# 02_MCU.net
KiCad netlist of a schematic drawn in Altium Designer
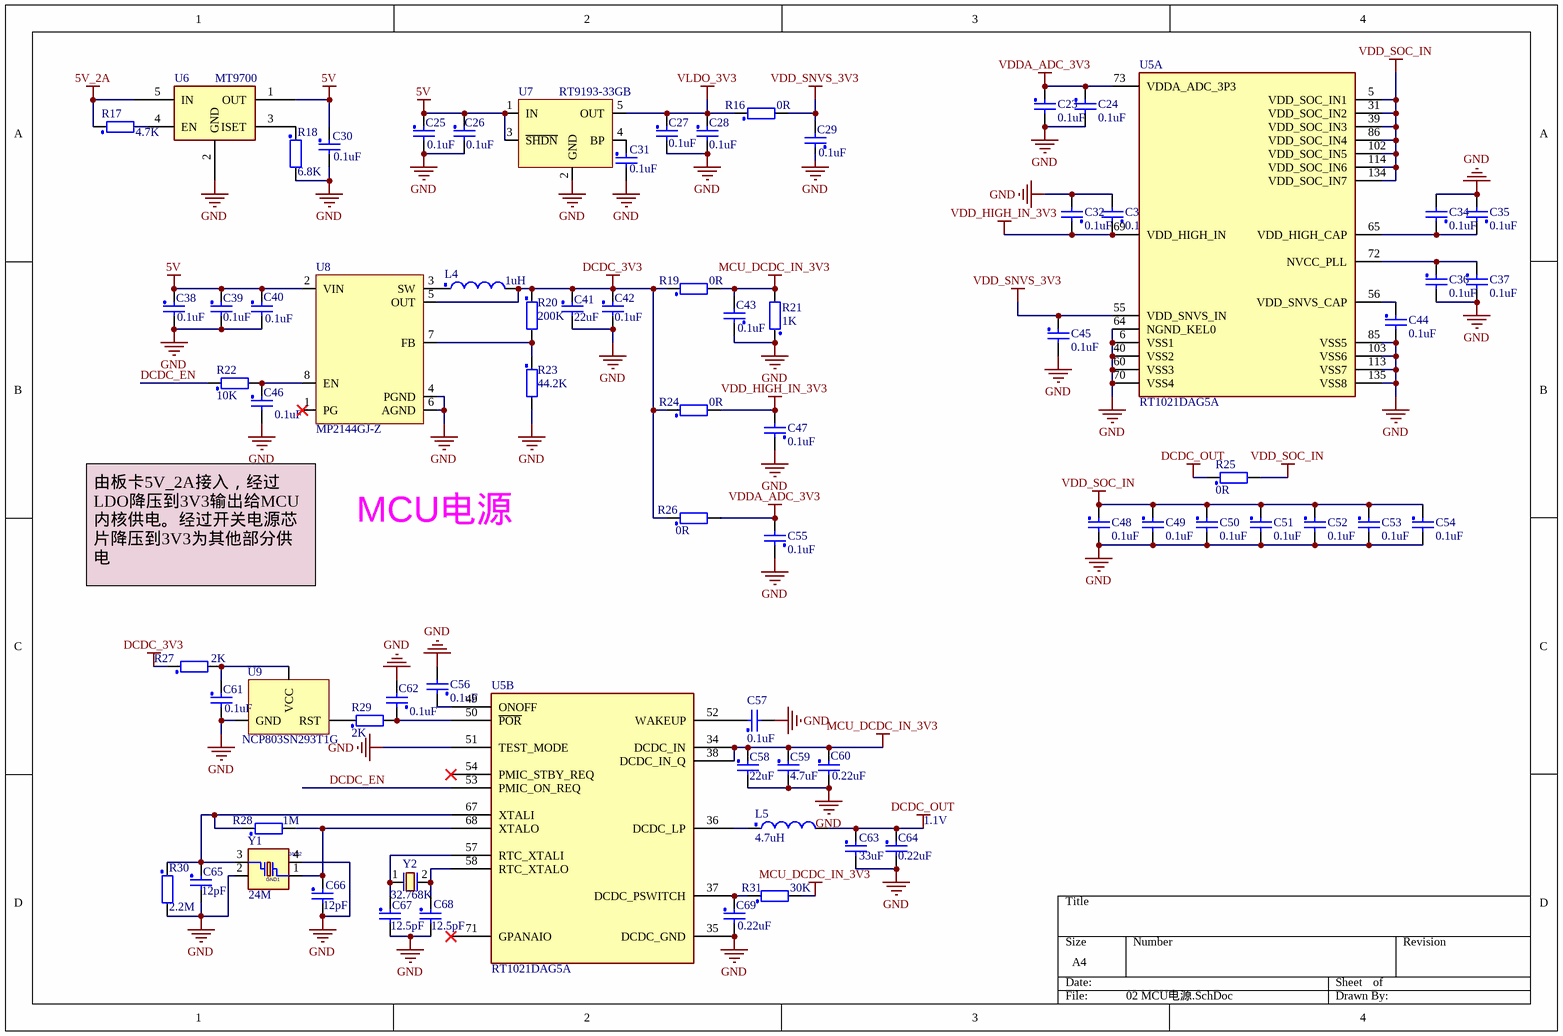
[diagram p0: 02 MCU电源.SchDoc]

(export (version "E")
  (design (tool "Eeschema 10.0.6"))
  (components
    (comp (ref "C23")
      (value "0.1uF")
      (footprint "cap0603")
      (description "贴片电容")
      (fields (field (name "PUBLISHER") "Altium Limited"))
      (libsource (lib "元件库") (part "Cap"))
    )
    (comp (ref "C24")
      (value "0.1uF")
      (footprint "cap0603")
      (description "贴片电容")
      (fields (field (name "PUBLISHER") "Altium Limited"))
      (libsource (lib "元件库") (part "Cap"))
    )
    (comp (ref "C25")
      (value "0.1uF")
      (footprint "cap0603")
      (description "贴片电容")
      (fields (field (name "PUBLISHER") "Altium Limited"))
      (libsource (lib "元件库") (part "Cap"))
    )
    (comp (ref "C26")
      (value "0.1uF")
      (footprint "cap0603")
      (description "贴片电容")
      (fields (field (name "PUBLISHER") "Altium Limited"))
      (libsource (lib "元件库") (part "Cap"))
    )
    (comp (ref "C27")
      (value "0.1uF")
      (footprint "cap0603")
      (description "贴片电容")
      (fields (field (name "PUBLISHER") "Altium Limited"))
      (libsource (lib "元件库") (part "Cap"))
    )
    (comp (ref "C28")
      (value "0.1uF")
      (footprint "cap0603")
      (description "贴片电容")
      (fields (field (name "PUBLISHER") "Altium Limited"))
      (libsource (lib "元件库") (part "Cap"))
    )
    (comp (ref "C29")
      (value "0.1uF")
      (footprint "cap0603")
      (description "贴片电容")
      (fields (field (name "PUBLISHER") "Altium Limited"))
      (libsource (lib "元件库") (part "Cap"))
    )
    (comp (ref "C30")
      (value "0.1uF")
      (footprint "cap0603")
      (description "贴片电容")
      (fields (field (name "PUBLISHER") "Altium Limited"))
      (libsource (lib "元件库") (part "Cap"))
    )
    (comp (ref "C31")
      (value "0.1uF")
      (footprint "cap0603")
      (description "贴片电容")
      (fields (field (name "PUBLISHER") "Altium Limited"))
      (libsource (lib "元件库") (part "Cap"))
    )
    (comp (ref "C32")
      (value "0.1uF")
      (footprint "cap0603")
      (description "贴片电容")
      (fields (field (name "PUBLISHER") "Altium Limited"))
      (libsource (lib "元件库") (part "Cap"))
    )
    (comp (ref "C33")
      (value "0.1uF")
      (footprint "cap0603")
      (description "贴片电容")
      (fields (field (name "PUBLISHER") "Altium Limited"))
      (libsource (lib "元件库") (part "Cap"))
    )
    (comp (ref "C34")
      (value "0.1uF")
      (footprint "cap0603")
      (description "贴片电容")
      (fields (field (name "PUBLISHER") "Altium Limited"))
      (libsource (lib "元件库") (part "Cap"))
    )
    (comp (ref "C35")
      (value "0.1uF")
      (footprint "cap0603")
      (description "贴片电容")
      (fields (field (name "PUBLISHER") "Altium Limited"))
      (libsource (lib "元件库") (part "Cap"))
    )
    (comp (ref "C36")
      (value "0.1uF")
      (footprint "cap0603")
      (description "贴片电容")
      (fields (field (name "PUBLISHER") "Altium Limited"))
      (libsource (lib "元件库") (part "Cap"))
    )
    (comp (ref "C37")
      (value "0.1uF")
      (footprint "cap0603")
      (description "贴片电容")
      (fields (field (name "PUBLISHER") "Altium Limited"))
      (libsource (lib "元件库") (part "Cap"))
    )
    (comp (ref "C38")
      (value "0.1uF")
      (footprint "cap0603")
      (description "贴片电容")
      (fields (field (name "PUBLISHER") "Altium Limited"))
      (libsource (lib "元件库") (part "Cap"))
    )
    (comp (ref "C39")
      (value "0.1uF")
      (footprint "cap0603")
      (description "贴片电容")
      (fields (field (name "PUBLISHER") "Altium Limited"))
      (libsource (lib "元件库") (part "Cap"))
    )
    (comp (ref "C40")
      (value "0.1uF")
      (footprint "cap0603")
      (description "贴片电容")
      (fields (field (name "PUBLISHER") "Altium Limited"))
      (libsource (lib "元件库") (part "Cap"))
    )
    (comp (ref "C41")
      (value "22uF")
      (footprint "CASE-A_3216")
      (description "钽电容")
      (fields (field (name "PUBLISHER") "Altium Limited"))
      (libsource (lib "元件库") (part "Cap"))
    )
    (comp (ref "C42")
      (value "0.1uF")
      (footprint "cap0603")
      (description "贴片电容")
      (fields (field (name "PUBLISHER") "Altium Limited"))
      (libsource (lib "元件库") (part "Cap"))
    )
    (comp (ref "C43")
      (value "0.1uF")
      (footprint "cap0603")
      (description "贴片电容")
      (fields (field (name "PUBLISHER") "Altium Limited"))
      (libsource (lib "元件库") (part "Cap"))
    )
    (comp (ref "C44")
      (value "0.1uF")
      (footprint "cap0603")
      (description "贴片电容")
      (fields (field (name "PUBLISHER") "Altium Limited"))
      (libsource (lib "元件库") (part "Cap"))
    )
    (comp (ref "C45")
      (value "0.1uF")
      (footprint "cap0603")
      (description "贴片电容")
      (fields (field (name "PUBLISHER") "Altium Limited"))
      (libsource (lib "元件库") (part "Cap"))
    )
    (comp (ref "C46")
      (value "0.1uF")
      (footprint "cap0603")
      (description "贴片电容")
      (fields (field (name "PUBLISHER") "Altium Limited"))
      (libsource (lib "元件库") (part "Cap"))
    )
    (comp (ref "C47")
      (value "0.1uF")
      (footprint "cap0603")
      (description "贴片电容")
      (fields (field (name "PUBLISHER") "Altium Limited"))
      (libsource (lib "元件库") (part "Cap"))
    )
    (comp (ref "C48")
      (value "0.1uF")
      (footprint "cap0603")
      (description "贴片电容")
      (fields (field (name "PUBLISHER") "Altium Limited"))
      (libsource (lib "元件库") (part "Cap"))
    )
    (comp (ref "C49")
      (value "0.1uF")
      (footprint "cap0603")
      (description "贴片电容")
      (fields (field (name "PUBLISHER") "Altium Limited"))
      (libsource (lib "元件库") (part "Cap"))
    )
    (comp (ref "C50")
      (value "0.1uF")
      (footprint "cap0603")
      (description "贴片电容")
      (fields (field (name "PUBLISHER") "Altium Limited"))
      (libsource (lib "元件库") (part "Cap"))
    )
    (comp (ref "C51")
      (value "0.1uF")
      (footprint "cap0603")
      (description "贴片电容")
      (fields (field (name "PUBLISHER") "Altium Limited"))
      (libsource (lib "元件库") (part "Cap"))
    )
    (comp (ref "C52")
      (value "0.1uF")
      (footprint "cap0603")
      (description "贴片电容")
      (fields (field (name "PUBLISHER") "Altium Limited"))
      (libsource (lib "元件库") (part "Cap"))
    )
    (comp (ref "C53")
      (value "0.1uF")
      (footprint "cap0603")
      (description "贴片电容")
      (fields (field (name "PUBLISHER") "Altium Limited"))
      (libsource (lib "元件库") (part "Cap"))
    )
    (comp (ref "C54")
      (value "0.1uF")
      (footprint "cap0603")
      (description "贴片电容")
      (fields (field (name "PUBLISHER") "Altium Limited"))
      (libsource (lib "元件库") (part "Cap"))
    )
    (comp (ref "C55")
      (value "0.1uF")
      (footprint "cap0603")
      (description "贴片电容")
      (fields (field (name "PUBLISHER") "Altium Limited"))
      (libsource (lib "元件库") (part "Cap"))
    )
    (comp (ref "C56")
      (value "0.1uF")
      (footprint "cap0603")
      (description "贴片电容")
      (fields (field (name "PUBLISHER") "Altium Limited"))
      (libsource (lib "元件库") (part "Cap"))
    )
    (comp (ref "C57")
      (value "0.1uF")
      (footprint "cap0603")
      (description "贴片电容")
      (fields (field (name "PUBLISHER") "Altium Limited"))
      (libsource (lib "元件库") (part "Cap"))
    )
    (comp (ref "C58")
      (value "22uF")
      (footprint "CASE-A_3216")
      (description "钽电容")
      (fields (field (name "PUBLISHER") "Altium Limited"))
      (libsource (lib "元件库") (part "Cap"))
    )
    (comp (ref "C59")
      (value "4.7uF")
      (footprint "cap0603")
      (description "贴片电容")
      (fields (field (name "PUBLISHER") "Altium Limited"))
      (libsource (lib "元件库") (part "Cap"))
    )
    (comp (ref "C60")
      (value "0.22uF")
      (footprint "cap0603")
      (description "贴片电容")
      (fields (field (name "PUBLISHER") "Altium Limited"))
      (libsource (lib "元件库") (part "Cap"))
    )
    (comp (ref "C61")
      (value "0.1uF")
      (footprint "cap0603")
      (description "贴片电容")
      (fields (field (name "PUBLISHER") "Altium Limited"))
      (libsource (lib "元件库") (part "Cap"))
    )
    (comp (ref "C62")
      (value "0.1uF")
      (footprint "cap0603")
      (description "贴片电容")
      (fields (field (name "PUBLISHER") "Altium Limited"))
      (libsource (lib "元件库") (part "Cap"))
    )
    (comp (ref "C63")
      (value "33uF")
      (footprint "CASE-A_3216")
      (description "钽电容")
      (fields (field (name "PUBLISHER") "Altium Limited"))
      (libsource (lib "元件库") (part "Cap"))
    )
    (comp (ref "C64")
      (value "0.22uF")
      (footprint "cap0603")
      (description "贴片电容")
      (fields (field (name "PUBLISHER") "Altium Limited"))
      (libsource (lib "元件库") (part "Cap"))
    )
    (comp (ref "C65")
      (value "12pF")
      (footprint "cap0603")
      (description "贴片电容")
      (fields (field (name "PUBLISHER") "Altium Limited"))
      (libsource (lib "元件库") (part "Cap"))
    )
    (comp (ref "C66")
      (value "12pF")
      (footprint "cap0603")
      (description "贴片电容")
      (fields (field (name "PUBLISHER") "Altium Limited"))
      (libsource (lib "元件库") (part "Cap"))
    )
    (comp (ref "C67")
      (value "12.5pF")
      (footprint "cap0603")
      (description "贴片电容")
      (fields (field (name "PUBLISHER") "Altium Limited"))
      (libsource (lib "元件库") (part "Cap"))
    )
    (comp (ref "C68")
      (value "12.5pF")
      (footprint "cap0603")
      (description "贴片电容")
      (fields (field (name "PUBLISHER") "Altium Limited"))
      (libsource (lib "元件库") (part "Cap"))
    )
    (comp (ref "C69")
      (value "0.22uF")
      (footprint "cap0603")
      (description "贴片电容")
      (fields (field (name "PUBLISHER") "Altium Limited"))
      (libsource (lib "元件库") (part "Cap"))
    )
    (comp (ref "L4")
      (value "1uH")
      (footprint "CD43")
      (description "贴片功率电感")
      (fields (field (name "PUBLISHER") "Altium Limited"))
      (libsource (lib "元件库") (part "Inductor"))
    )
    (comp (ref "L5")
      (value "4.7uH")
      (footprint "CD43")
      (description "贴片功率电感")
      (fields (field (name "PUBLISHER") "Altium Limited"))
      (libsource (lib "元件库") (part "Inductor"))
    )
    (comp (ref "R16")
      (value "0R")
      (footprint "res0603")
      (description "贴片电阻")
      (fields (field (name "PUBLISHER") "Altium Limited"))
      (libsource (lib "") (part "Res_2"))
    )
    (comp (ref "R17")
      (value "4.7K")
      (footprint "res0603")
      (description "贴片电阻")
      (fields (field (name "PUBLISHER") "Altium Limited"))
      (libsource (lib "") (part "Res_2"))
    )
    (comp (ref "R18")
      (value "6.8K")
      (footprint "res0603")
      (description "贴片电阻")
      (fields (field (name "PUBLISHER") "Altium Limited"))
      (libsource (lib "元件库") (part "Res"))
    )
    (comp (ref "R19")
      (value "0R")
      (footprint "res0603")
      (description "贴片电阻")
      (fields (field (name "PUBLISHER") "Altium Limited"))
      (libsource (lib "") (part "Res_2"))
    )
    (comp (ref "R20")
      (value "200K")
      (footprint "res0603")
      (description "贴片电阻")
      (fields (field (name "PUBLISHER") "Altium Limited"))
      (libsource (lib "元件库") (part "Res"))
    )
    (comp (ref "R21")
      (value "1K")
      (footprint "res0603")
      (description "贴片电阻")
      (fields (field (name "PUBLISHER") "Altium Limited"))
      (libsource (lib "") (part "Res_1"))
    )
    (comp (ref "R22")
      (value "10K")
      (footprint "res0603")
      (description "贴片电阻")
      (fields (field (name "PUBLISHER") "Altium Limited"))
      (libsource (lib "") (part "Res_2"))
    )
    (comp (ref "R23")
      (value "44.2K")
      (footprint "res0603")
      (description "贴片电阻")
      (fields (field (name "PUBLISHER") "Altium Limited"))
      (libsource (lib "元件库") (part "Res"))
    )
    (comp (ref "R24")
      (value "0R")
      (footprint "res0603")
      (description "贴片电阻")
      (fields (field (name "PUBLISHER") "Altium Limited"))
      (libsource (lib "") (part "Res_2"))
    )
    (comp (ref "R25")
      (value "0R")
      (footprint "res0603")
      (description "贴片电阻")
      (fields (field (name "PUBLISHER") "Altium Limited"))
      (libsource (lib "") (part "Res_2"))
    )
    (comp (ref "R26")
      (value "0R")
      (footprint "res0603")
      (description "贴片电阻")
      (fields (field (name "PUBLISHER") "Altium Limited"))
      (libsource (lib "") (part "Res_2"))
    )
    (comp (ref "R27")
      (value "2K")
      (footprint "res0603")
      (description "贴片电阻")
      (fields (field (name "PUBLISHER") "Altium Limited"))
      (libsource (lib "") (part "Res_2"))
    )
    (comp (ref "R28")
      (value "1M")
      (footprint "res0603")
      (description "贴片电阻")
      (fields (field (name "PUBLISHER") "Altium Limited"))
      (libsource (lib "") (part "Res_2"))
    )
    (comp (ref "R29")
      (value "2K")
      (footprint "res0603")
      (description "贴片电阻")
      (fields (field (name "PUBLISHER") "Altium Limited"))
      (libsource (lib "") (part "Res_2"))
    )
    (comp (ref "R30")
      (value "2.2M")
      (footprint "res0603")
      (description "贴片电阻")
      (fields (field (name "PUBLISHER") "Altium Limited"))
      (libsource (lib "元件库") (part "Res"))
    )
    (comp (ref "R31")
      (value "30K")
      (footprint "res0603")
      (description "贴片电阻")
      (fields (field (name "PUBLISHER") "Altium Limited"))
      (libsource (lib "") (part "Res_2"))
    )
    (comp (ref "U5")
      (value "RT1021DAG5A")
      (footprint "LQFP144")
      (description "Cortex-M7 500MHZ 1.3V")
      (libsource (lib "元件库") (part "RT1021DAG5A"))
    )
    (comp (ref "U6")
      (value "MT9700")
      (footprint "SOT23-5")
      (description "功率开关，SY6280AAC")
      (libsource (lib "元件库") (part "MT9700"))
    )
    (comp (ref "U7")
      (value "RT9193-33GB")
      (footprint "SOT23-5")
      (description "线性稳压芯片3.3V  300mA  SOT23-5")
      (libsource (lib "元件库") (part "RT9193-33GB"))
    )
    (comp (ref "U8")
      (value "MP2144GJ-Z")
      (footprint "TSOT23-8")
      (description "开关稳压芯片 0.6V 2A 2.5-5.5V TSOT23-8")
      (libsource (lib "元件库") (part "MP2144GJ-Z"))
    )
    (comp (ref "U9")
      (value "NCP803SN293T1G")
      (footprint "SOT-23-3")
      (description "mcu复位芯片")
      (libsource (lib "元件库") (part "NCP803SN293T1G"))
    )
    (comp (ref "Y1")
      (value "24M")
      (footprint "SMD3225")
      (description "无源晶振24MHZ 12pF 3.2X2.5MM SMD")
      (fields (field (name "Comment") "24MHz"))
      (libsource (lib "元件库") (part "CRYSTAL_JXS63"))
    )
    (comp (ref "Y2")
      (value "32.768K")
      (footprint "SMD3215")
      (description "晶振 32.768KHZ 12.5PF")
      (libsource (lib "元件库") (part "CRYSTAL"))
    )
  )
  (nets
    (net (code "1") (name "/DCDC_EN") (class "Default")
      (node (ref "R22") (pin "1") (pinfunction "1_1") (pintype "passive"))
      (node (ref "U5") (pin "53") (pinfunction "PMIC_ON_REQ_53") (pintype "passive"))
    )
    (net (code "2") (name "5V") (class "Default")
      (node (ref "C25") (pin "1") (pinfunction "1_1") (pintype "passive"))
      (node (ref "C26") (pin "1") (pinfunction "1_1") (pintype "passive"))
      (node (ref "C30") (pin "1") (pinfunction "1_1") (pintype "passive"))
      (node (ref "C38") (pin "1") (pinfunction "1_1") (pintype "passive"))
      (node (ref "C39") (pin "1") (pinfunction "1_1") (pintype "passive"))
      (node (ref "C40") (pin "1") (pinfunction "1_1") (pintype "passive"))
      (node (ref "U6") (pin "1") (pinfunction "OUT_1") (pintype "passive"))
      (node (ref "U7") (pin "1") (pinfunction "IN_1") (pintype "passive"))
      (node (ref "U7") (pin "3") (pinfunction "~{SHDN}_3") (pintype "passive"))
      (node (ref "U8") (pin "2") (pinfunction "VIN_2") (pintype "passive"))
    )
    (net (code "3") (name "5V_2A") (class "Default")
      (node (ref "R17") (pin "1") (pinfunction "1_1") (pintype "passive"))
      (node (ref "U6") (pin "5") (pinfunction "IN_5") (pintype "passive"))
    )
    (net (code "4") (name "DCDC_3V3") (class "Default")
      (node (ref "C41") (pin "1") (pinfunction "1_1") (pintype "passive"))
      (node (ref "C42") (pin "1") (pinfunction "1_1") (pintype "passive"))
      (node (ref "L4") (pin "2") (pinfunction "2_2") (pintype "passive"))
      (node (ref "R19") (pin "1") (pinfunction "1_1") (pintype "passive"))
      (node (ref "R20") (pin "1") (pinfunction "1_1") (pintype "passive"))
      (node (ref "R24") (pin "1") (pinfunction "1_1") (pintype "passive"))
      (node (ref "R26") (pin "1") (pinfunction "1_1") (pintype "passive"))
      (node (ref "R27") (pin "1") (pinfunction "1_1") (pintype "passive"))
      (node (ref "U8") (pin "5") (pinfunction "OUT_5") (pintype "passive"))
    )
    (net (code "5") (name "DCDC_OUT") (class "Default")
      (node (ref "C63") (pin "1") (pinfunction "1_1") (pintype "passive"))
      (node (ref "C64") (pin "1") (pinfunction "1_1") (pintype "passive"))
      (node (ref "L5") (pin "2") (pinfunction "2_2") (pintype "passive"))
      (node (ref "R25") (pin "1") (pinfunction "1_1") (pintype "passive"))
    )
    (net (code "6") (name "GND") (class "Default")
      (node (ref "C23") (pin "2") (pinfunction "2_2") (pintype "passive"))
      (node (ref "C24") (pin "2") (pinfunction "2_2") (pintype "passive"))
      (node (ref "C25") (pin "2") (pinfunction "2_2") (pintype "passive"))
      (node (ref "C26") (pin "2") (pinfunction "2_2") (pintype "passive"))
      (node (ref "C27") (pin "2") (pinfunction "2_2") (pintype "passive"))
      (node (ref "C28") (pin "2") (pinfunction "2_2") (pintype "passive"))
      (node (ref "C29") (pin "1") (pinfunction "1_1") (pintype "passive"))
      (node (ref "C30") (pin "2") (pinfunction "2_2") (pintype "passive"))
      (node (ref "C31") (pin "2") (pinfunction "2_2") (pintype "passive"))
      (node (ref "C32") (pin "2") (pinfunction "2_2") (pintype "passive"))
      (node (ref "C33") (pin "2") (pinfunction "2_2") (pintype "passive"))
      (node (ref "C34") (pin "2") (pinfunction "2_2") (pintype "passive"))
      (node (ref "C35") (pin "2") (pinfunction "2_2") (pintype "passive"))
      (node (ref "C36") (pin "2") (pinfunction "2_2") (pintype "passive"))
      (node (ref "C37") (pin "2") (pinfunction "2_2") (pintype "passive"))
      (node (ref "C38") (pin "2") (pinfunction "2_2") (pintype "passive"))
      (node (ref "C39") (pin "2") (pinfunction "2_2") (pintype "passive"))
      (node (ref "C40") (pin "2") (pinfunction "2_2") (pintype "passive"))
      (node (ref "C41") (pin "2") (pinfunction "2_2") (pintype "passive"))
      (node (ref "C42") (pin "2") (pinfunction "2_2") (pintype "passive"))
      (node (ref "C43") (pin "1") (pinfunction "1_1") (pintype "passive"))
      (node (ref "C44") (pin "2") (pinfunction "2_2") (pintype "passive"))
      (node (ref "C45") (pin "2") (pinfunction "2_2") (pintype "passive"))
      (node (ref "C46") (pin "2") (pinfunction "2_2") (pintype "passive"))
      (node (ref "C47") (pin "1") (pinfunction "1_1") (pintype "passive"))
      (node (ref "C48") (pin "2") (pinfunction "2_2") (pintype "passive"))
      (node (ref "C49") (pin "2") (pinfunction "2_2") (pintype "passive"))
      (node (ref "C50") (pin "2") (pinfunction "2_2") (pintype "passive"))
      (node (ref "C51") (pin "2") (pinfunction "2_2") (pintype "passive"))
      (node (ref "C52") (pin "2") (pinfunction "2_2") (pintype "passive"))
      (node (ref "C53") (pin "2") (pinfunction "2_2") (pintype "passive"))
      (node (ref "C54") (pin "2") (pinfunction "2_2") (pintype "passive"))
      (node (ref "C55") (pin "1") (pinfunction "1_1") (pintype "passive"))
      (node (ref "C56") (pin "2") (pinfunction "2_2") (pintype "passive"))
      (node (ref "C57") (pin "2") (pinfunction "2_2") (pintype "passive"))
      (node (ref "C58") (pin "2") (pinfunction "2_2") (pintype "passive"))
      (node (ref "C59") (pin "2") (pinfunction "2_2") (pintype "passive"))
      (node (ref "C60") (pin "2") (pinfunction "2_2") (pintype "passive"))
      (node (ref "C61") (pin "2") (pinfunction "2_2") (pintype "passive"))
      (node (ref "C62") (pin "2") (pinfunction "2_2") (pintype "passive"))
      (node (ref "C63") (pin "2") (pinfunction "2_2") (pintype "passive"))
      (node (ref "C64") (pin "2") (pinfunction "2_2") (pintype "passive"))
      (node (ref "C65") (pin "2") (pinfunction "2_2") (pintype "passive"))
      (node (ref "C66") (pin "2") (pinfunction "2_2") (pintype "passive"))
      (node (ref "C67") (pin "2") (pinfunction "2_2") (pintype "passive"))
      (node (ref "C68") (pin "2") (pinfunction "2_2") (pintype "passive"))
      (node (ref "C69") (pin "2") (pinfunction "2_2") (pintype "passive"))
      (node (ref "R18") (pin "2") (pinfunction "2_2") (pintype "passive"))
      (node (ref "R21") (pin "1") (pinfunction "1_1") (pintype "passive"))
      (node (ref "R23") (pin "2") (pinfunction "2_2") (pintype "passive"))
      (node (ref "R30") (pin "2") (pinfunction "2_2") (pintype "passive"))
      (node (ref "U5") (pin "103") (pinfunction "VSS6_103") (pintype "power_in"))
      (node (ref "U5") (pin "113") (pinfunction "VSS7_113") (pintype "power_in"))
      (node (ref "U5") (pin "135") (pinfunction "VSS8_135") (pintype "power_in"))
      (node (ref "U5") (pin "35") (pinfunction "DCDC_GND_35") (pintype "power_in"))
      (node (ref "U5") (pin "40") (pinfunction "VSS2_40") (pintype "power_in"))
      (node (ref "U5") (pin "51") (pinfunction "TEST_MODE_51") (pintype "passive"))
      (node (ref "U5") (pin "6") (pinfunction "VSS1_6") (pintype "power_in"))
      (node (ref "U5") (pin "60") (pinfunction "VSS3_60") (pintype "power_in"))
      (node (ref "U5") (pin "64") (pinfunction "NGND_KEL0_64") (pintype "power_in"))
      (node (ref "U5") (pin "70") (pinfunction "VSS4_70") (pintype "power_in"))
      (node (ref "U5") (pin "85") (pinfunction "VSS5_85") (pintype "power_in"))
      (node (ref "U6") (pin "2") (pinfunction "GND_2") (pintype "passive"))
      (node (ref "U7") (pin "2") (pinfunction "GND_2") (pintype "passive"))
      (node (ref "U8") (pin "4") (pinfunction "PGND_4") (pintype "passive"))
      (node (ref "U8") (pin "6") (pinfunction "AGND_6") (pintype "passive"))
      (node (ref "U9") (pin "1") (pinfunction "GND_1") (pintype "passive"))
      (node (ref "Y1") (pin "2") (pinfunction "GND1_2") (pintype "power_in"))
      (node (ref "Y1") (pin "4") (pinfunction "GND2_4") (pintype "power_in"))
    )
    (net (code "7") (name "MCU_DCDC_IN_3V3") (class "Default")
      (node (ref "C43") (pin "2") (pinfunction "2_2") (pintype "passive"))
      (node (ref "C58") (pin "1") (pinfunction "1_1") (pintype "passive"))
      (node (ref "C59") (pin "1") (pinfunction "1_1") (pintype "passive"))
      (node (ref "C60") (pin "1") (pinfunction "1_1") (pintype "passive"))
      (node (ref "R19") (pin "2") (pinfunction "2_2") (pintype "passive"))
      (node (ref "R21") (pin "2") (pinfunction "2_2") (pintype "passive"))
      (node (ref "R31") (pin "2") (pinfunction "2_2") (pintype "passive"))
      (node (ref "U5") (pin "34") (pinfunction "DCDC_IN_34") (pintype "passive"))
      (node (ref "U5") (pin "38") (pinfunction "DCDC_IN_Q_38") (pintype "passive"))
    )
    (net (code "8") (name "Net-(U5A-NVCC_PLL)") (class "Default")
      (node (ref "C36") (pin "1") (pinfunction "1_1") (pintype "passive"))
      (node (ref "C37") (pin "1") (pinfunction "1_1") (pintype "passive"))
      (node (ref "U5") (pin "72") (pinfunction "NVCC_PLL_72") (pintype "power_in"))
    )
    (net (code "9") (name "Net-(U5A-VDD_HIGH_CAP)") (class "Default")
      (node (ref "C34") (pin "1") (pinfunction "1_1") (pintype "passive"))
      (node (ref "C35") (pin "1") (pinfunction "1_1") (pintype "passive"))
      (node (ref "U5") (pin "65") (pinfunction "VDD_HIGH_CAP_65") (pintype "power_in"))
    )
    (net (code "10") (name "Net-(U5A-VDD_SNVS_CAP)") (class "Default")
      (node (ref "C44") (pin "1") (pinfunction "1_1") (pintype "passive"))
      (node (ref "U5") (pin "56") (pinfunction "VDD_SNVS_CAP_56") (pintype "power_in"))
    )
    (net (code "11") (name "Net-(U5B-DCDC_LP)") (class "Default")
      (node (ref "L5") (pin "1") (pinfunction "1_1") (pintype "passive"))
      (node (ref "U5") (pin "36") (pinfunction "DCDC_LP_36") (pintype "power_in"))
    )
    (net (code "12") (name "Net-(U5B-DCDC_PSWITCH)") (class "Default")
      (node (ref "C69") (pin "1") (pinfunction "1_1") (pintype "passive"))
      (node (ref "R31") (pin "1") (pinfunction "1_1") (pintype "passive"))
      (node (ref "U5") (pin "37") (pinfunction "DCDC_PSWITCH_37") (pintype "passive"))
    )
    (net (code "13") (name "Net-(U5B-ONOFF)") (class "Default")
      (node (ref "C56") (pin "1") (pinfunction "1_1") (pintype "passive"))
      (node (ref "U5") (pin "49") (pinfunction "ONOFF_49") (pintype "passive"))
    )
    (net (code "14") (name "Net-(U5B-RTC_XTALI)") (class "Default")
      (node (ref "C67") (pin "1") (pinfunction "1_1") (pintype "passive"))
      (node (ref "U5") (pin "57") (pinfunction "RTC_XTALI_57") (pintype "passive"))
      (node (ref "Y2") (pin "1") (pinfunction "1_1") (pintype "passive"))
    )
    (net (code "15") (name "Net-(U5B-RTC_XTALO)") (class "Default")
      (node (ref "C68") (pin "1") (pinfunction "1_1") (pintype "passive"))
      (node (ref "U5") (pin "58") (pinfunction "RTC_XTALO_58") (pintype "passive"))
      (node (ref "Y2") (pin "2") (pinfunction "2_2") (pintype "passive"))
    )
    (net (code "16") (name "Net-(U5B-WAKEUP)") (class "Default")
      (node (ref "C57") (pin "1") (pinfunction "1_1") (pintype "passive"))
      (node (ref "U5") (pin "52") (pinfunction "WAKEUP_52") (pintype "passive"))
    )
    (net (code "17") (name "Net-(U5B-XTALI)") (class "Default")
      (node (ref "C65") (pin "1") (pinfunction "1_1") (pintype "passive"))
      (node (ref "R28") (pin "1") (pinfunction "1_1") (pintype "passive"))
      (node (ref "R30") (pin "1") (pinfunction "1_1") (pintype "passive"))
      (node (ref "U5") (pin "67") (pinfunction "XTALI_67") (pintype "passive"))
      (node (ref "Y1") (pin "3") (pinfunction "3_3") (pintype "passive"))
    )
    (net (code "18") (name "Net-(U5B-XTALO)") (class "Default")
      (node (ref "C66") (pin "1") (pinfunction "1_1") (pintype "passive"))
      (node (ref "R28") (pin "2") (pinfunction "2_2") (pintype "passive"))
      (node (ref "U5") (pin "68") (pinfunction "XTALO_68") (pintype "passive"))
      (node (ref "Y1") (pin "1") (pinfunction "1_1") (pintype "passive"))
    )
    (net (code "19") (name "Net-(U5B-~{POR})") (class "Default")
      (node (ref "C62") (pin "1") (pinfunction "1_1") (pintype "passive"))
      (node (ref "R29") (pin "2") (pinfunction "2_2") (pintype "passive"))
      (node (ref "U5") (pin "50") (pinfunction "~{POR}_50") (pintype "passive"))
    )
    (net (code "20") (name "Net-(U6-EN)") (class "Default")
      (node (ref "R17") (pin "2") (pinfunction "2_2") (pintype "passive"))
      (node (ref "U6") (pin "4") (pinfunction "EN_4") (pintype "passive"))
    )
    (net (code "21") (name "Net-(U6-ISET)") (class "Default")
      (node (ref "R18") (pin "1") (pinfunction "1_1") (pintype "passive"))
      (node (ref "U6") (pin "3") (pinfunction "ISET_3") (pintype "passive"))
    )
    (net (code "22") (name "Net-(U7-BP)") (class "Default")
      (node (ref "C31") (pin "1") (pinfunction "1_1") (pintype "passive"))
      (node (ref "U7") (pin "4") (pinfunction "BP_4") (pintype "passive"))
    )
    (net (code "23") (name "Net-(U8-EN)") (class "Default")
      (node (ref "C46") (pin "1") (pinfunction "1_1") (pintype "passive"))
      (node (ref "R22") (pin "2") (pinfunction "2_2") (pintype "passive"))
      (node (ref "U8") (pin "8") (pinfunction "EN_8") (pintype "passive"))
    )
    (net (code "24") (name "Net-(U8-FB)") (class "Default")
      (node (ref "R20") (pin "2") (pinfunction "2_2") (pintype "passive"))
      (node (ref "R23") (pin "1") (pinfunction "1_1") (pintype "passive"))
      (node (ref "U8") (pin "7") (pinfunction "FB_7") (pintype "passive"))
    )
    (net (code "25") (name "Net-(U8-SW)") (class "Default")
      (node (ref "L4") (pin "1") (pinfunction "1_1") (pintype "passive"))
      (node (ref "U8") (pin "3") (pinfunction "SW_3") (pintype "passive"))
    )
    (net (code "26") (name "Net-(U9-RST)") (class "Default")
      (node (ref "R29") (pin "1") (pinfunction "1_1") (pintype "passive"))
      (node (ref "U9") (pin "2") (pinfunction "RST_2") (pintype "passive"))
    )
    (net (code "27") (name "Net-(U9-VCC)") (class "Default")
      (node (ref "C61") (pin "1") (pinfunction "1_1") (pintype "passive"))
      (node (ref "R27") (pin "2") (pinfunction "2_2") (pintype "passive"))
      (node (ref "U9") (pin "3") (pinfunction "VCC_3") (pintype "passive"))
    )
    (net (code "28") (name "VDDA_ADC_3V3") (class "Default")
      (node (ref "C23") (pin "1") (pinfunction "1_1") (pintype "passive"))
      (node (ref "C24") (pin "1") (pinfunction "1_1") (pintype "passive"))
      (node (ref "C55") (pin "2") (pinfunction "2_2") (pintype "passive"))
      (node (ref "R26") (pin "2") (pinfunction "2_2") (pintype "passive"))
      (node (ref "U5") (pin "73") (pinfunction "VDDA_ADC_3P3_73") (pintype "power_in"))
    )
    (net (code "29") (name "VDD_HIGH_IN_3V3") (class "Default")
      (node (ref "C32") (pin "1") (pinfunction "1_1") (pintype "passive"))
      (node (ref "C33") (pin "1") (pinfunction "1_1") (pintype "passive"))
      (node (ref "C47") (pin "2") (pinfunction "2_2") (pintype "passive"))
      (node (ref "R24") (pin "2") (pinfunction "2_2") (pintype "passive"))
      (node (ref "U5") (pin "69") (pinfunction "VDD_HIGH_IN_69") (pintype "power_in"))
    )
    (net (code "30") (name "VDD_SNVS_3V3") (class "Default")
      (node (ref "C29") (pin "2") (pinfunction "2_2") (pintype "passive"))
      (node (ref "C45") (pin "1") (pinfunction "1_1") (pintype "passive"))
      (node (ref "R16") (pin "2") (pinfunction "2_2") (pintype "passive"))
      (node (ref "U5") (pin "55") (pinfunction "VDD_SNVS_IN_55") (pintype "power_in"))
    )
    (net (code "31") (name "VDD_SOC_IN") (class "Default")
      (node (ref "C48") (pin "1") (pinfunction "1_1") (pintype "passive"))
      (node (ref "C49") (pin "1") (pinfunction "1_1") (pintype "passive"))
      (node (ref "C50") (pin "1") (pinfunction "1_1") (pintype "passive"))
      (node (ref "C51") (pin "1") (pinfunction "1_1") (pintype "passive"))
      (node (ref "C52") (pin "1") (pinfunction "1_1") (pintype "passive"))
      (node (ref "C53") (pin "1") (pinfunction "1_1") (pintype "passive"))
      (node (ref "C54") (pin "1") (pinfunction "1_1") (pintype "passive"))
      (node (ref "R25") (pin "2") (pinfunction "2_2") (pintype "passive"))
      (node (ref "U5") (pin "102") (pinfunction "VDD_SOC_IN5_102") (pintype "power_in"))
      (node (ref "U5") (pin "114") (pinfunction "VDD_SOC_IN6_114") (pintype "power_in"))
      (node (ref "U5") (pin "134") (pinfunction "VDD_SOC_IN7_134") (pintype "power_in"))
      (node (ref "U5") (pin "31") (pinfunction "VDD_SOC_IN2_31") (pintype "power_in"))
      (node (ref "U5") (pin "39") (pinfunction "VDD_SOC_IN3_39") (pintype "power_in"))
      (node (ref "U5") (pin "5") (pinfunction "VDD_SOC_IN1_5") (pintype "power_in"))
      (node (ref "U5") (pin "86") (pinfunction "VDD_SOC_IN4_86") (pintype "power_in"))
    )
    (net (code "32") (name "VLDO_3V3") (class "Default")
      (node (ref "C27") (pin "1") (pinfunction "1_1") (pintype "passive"))
      (node (ref "C28") (pin "1") (pinfunction "1_1") (pintype "passive"))
      (node (ref "R16") (pin "1") (pinfunction "1_1") (pintype "passive"))
      (node (ref "U7") (pin "5") (pinfunction "OUT_5") (pintype "passive"))
    )
    (net (code "33") (name "unconnected-(U5B-GPANAIO-Pad71)") (class "Default")
      (node (ref "U5") (pin "71") (pinfunction "GPANAIO_71") (pintype "power_in+no_connect"))
    )
    (net (code "34") (name "unconnected-(U5B-PMIC_STBY_REQ-Pad54)") (class "Default")
      (node (ref "U5") (pin "54") (pinfunction "PMIC_STBY_REQ_54") (pintype "passive+no_connect"))
    )
    (net (code "35") (name "unconnected-(U8-PG-Pad1)") (class "Default")
      (node (ref "U8") (pin "1") (pinfunction "PG_1") (pintype "passive+no_connect"))
    )
  )
)
